# pad2console.net
KiCad netlist of a schematic drawn in EAGLE
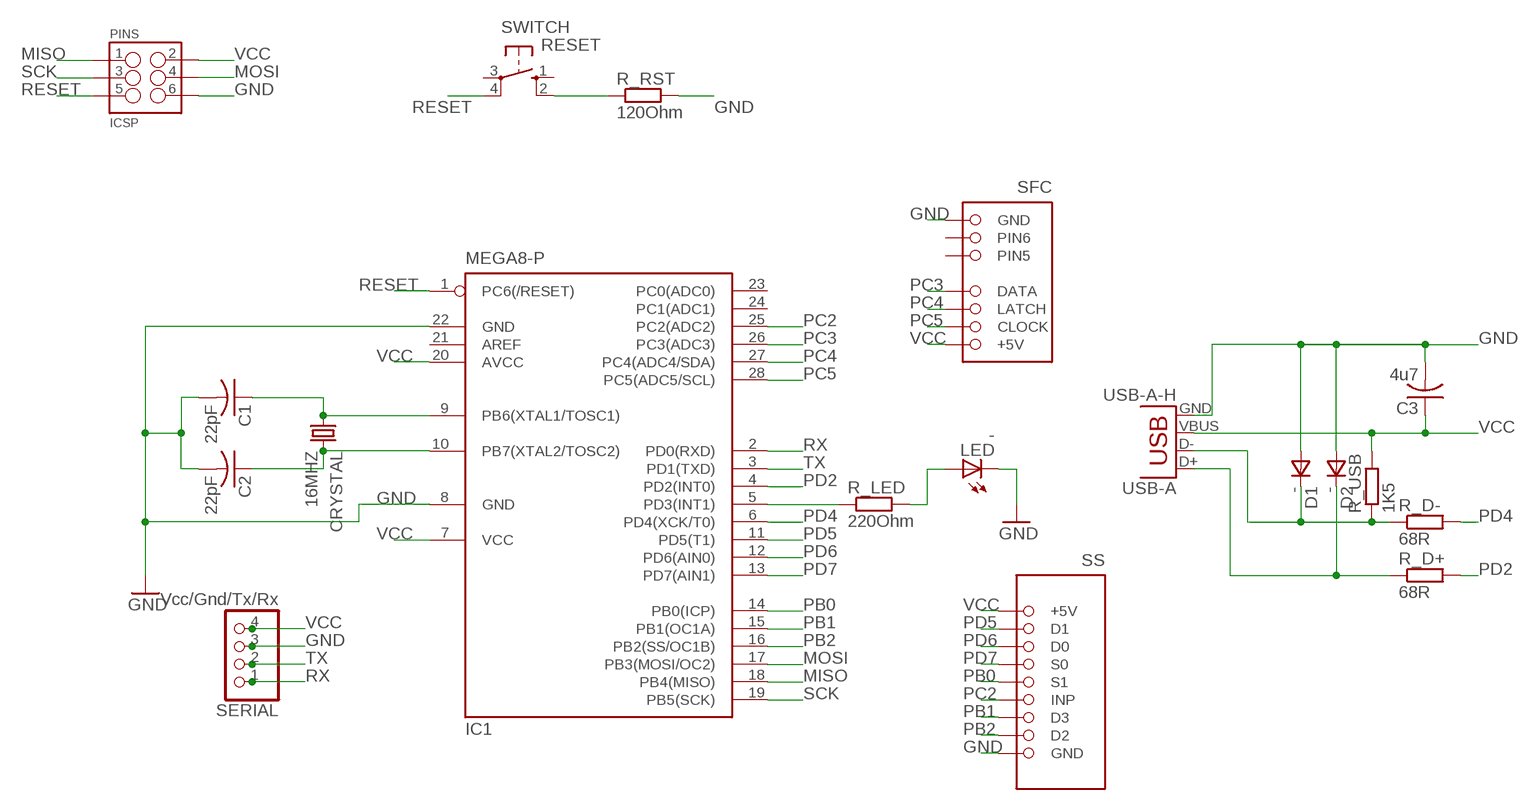
[diagram p0: schematic, sheet 1]

(export (version "E")
  (design (tool "Eeschema 10.0.6"))
  (components
    (comp (ref "C1")
      (value "22pF")
      (footprint "eagle-import:C050-024X044")
      (libsource (lib "eagle-import") (part "C-US050-024X044"))
    )
    (comp (ref "C2")
      (value "22pF")
      (footprint "eagle-import:C050-024X044")
      (libsource (lib "eagle-import") (part "C-US050-024X044"))
    )
    (comp (ref "C3")
      (value "4u7")
      (footprint "eagle-import:C050-024X044")
      (libsource (lib "eagle-import") (part "C-US050-024X044"))
    )
    (comp (ref "CRYSTAL")
      (value "16MHZ")
      (footprint "eagle-import:HC49_S")
      (libsource (lib "eagle-import") (part "CRYSTALHC49S"))
    )
    (comp (ref "D1")
      (value "-")
      (footprint "eagle-import:E2LINE")
      (libsource (lib "eagle-import") (part "D_E2L"))
    )
    (comp (ref "D2")
      (value "-")
      (footprint "eagle-import:E2LINE")
      (libsource (lib "eagle-import") (part "D_E2L"))
    )
    (comp (ref "IC1")
      (value "MEGA8-P")
      (footprint "eagle-import:DIL28-3")
      (libsource (lib "eagle-import") (part "MEGA8-P"))
    )
    (comp (ref "LED")
      (value "-")
      (footprint "eagle-import:LD260")
      (libsource (lib "eagle-import") (part "LEDLD260"))
    )
    (comp (ref "PINS")
      (value "ICSP")
      (footprint "eagle-import:2X3-SHROUDED")
      (libsource (lib "eagle-import") (part "M03X2SHROUD"))
    )
    (comp (ref "R_D+")
      (value "68R")
      (footprint "eagle-import:0204_5")
      (libsource (lib "eagle-import") (part "R-EU_0204/5"))
    )
    (comp (ref "R_D-")
      (value "68R")
      (footprint "eagle-import:0204_5")
      (libsource (lib "eagle-import") (part "R-EU_0204/5"))
    )
    (comp (ref "R_LED")
      (value "220Ohm")
      (footprint "eagle-import:0204_5")
      (libsource (lib "eagle-import") (part "R-EU_0204/5"))
    )
    (comp (ref "R_RST")
      (value "120Ohm")
      (footprint "eagle-import:0204_5")
      (libsource (lib "eagle-import") (part "R-EU_0204/5"))
    )
    (comp (ref "R_USB")
      (value "1K5")
      (footprint "eagle-import:0204_5")
      (libsource (lib "eagle-import") (part "R-EU_0204/5"))
    )
    (comp (ref "SERIAL")
      (value "Vcc/Gnd/Tx/Rx")
      (footprint "eagle-import:1X04")
      (libsource (lib "eagle-import") (part "PINHD-1X4"))
    )
    (comp (ref "SFC")
      (value "SFC_PIN")
      (footprint "eagle-import:SFC_PIN")
      (libsource (lib "eagle-import") (part "SFC_PIN"))
    )
    (comp (ref "SS")
      (value "SS_PIN")
      (footprint "eagle-import:SS_PIN")
      (libsource (lib "eagle-import") (part "SS_PIN"))
    )
    (comp (ref "SWITCH")
      (value "RESET")
      (footprint "eagle-import:B3F-10XX")
      (fields (field (name "MPN") "B3F-1000"))
      (libsource (lib "eagle-import") (part "10-XX"))
    )
    (comp (ref "USB-A")
      (value "USB-A-H")
      (footprint "eagle-import:USB-A-H")
      (libsource (lib "eagle-import") (part "USB-A-H"))
    )
  )
  (nets
    (net (code "1") (name "/MISO") (class "Default")
      (node (ref "IC1") (pin "18") (pinfunction "PB4(MISO)_18") (pintype "bidirectional"))
      (node (ref "PINS") (pin "1") (pinfunction "1_1") (pintype "bidirectional"))
    )
    (net (code "2") (name "/MOSI") (class "Default")
      (node (ref "IC1") (pin "17") (pinfunction "PB3(MOSI/OC2)_17") (pintype "bidirectional"))
      (node (ref "PINS") (pin "4") (pinfunction "4_4") (pintype "bidirectional"))
    )
    (net (code "3") (name "/PB0") (class "Default")
      (node (ref "IC1") (pin "14") (pinfunction "PB0(ICP)_14") (pintype "bidirectional"))
      (node (ref "SS") (pin "PIN5") (pinfunction "S1_PIN5") (pintype "bidirectional"))
    )
    (net (code "4") (name "/PB1") (class "Default")
      (node (ref "IC1") (pin "15") (pinfunction "PB1(OC1A)_15") (pintype "bidirectional"))
      (node (ref "SS") (pin "PIN7") (pinfunction "D3_PIN7") (pintype "bidirectional"))
    )
    (net (code "5") (name "/PB2") (class "Default")
      (node (ref "IC1") (pin "16") (pinfunction "PB2(SS/OC1B)_16") (pintype "bidirectional"))
      (node (ref "SS") (pin "PIN8") (pinfunction "D2_PIN8") (pintype "bidirectional"))
    )
    (net (code "6") (name "/PC2") (class "Default")
      (node (ref "IC1") (pin "25") (pinfunction "PC2(ADC2)_25") (pintype "bidirectional"))
      (node (ref "SS") (pin "PIN6") (pinfunction "INP_PIN6") (pintype "bidirectional"))
    )
    (net (code "7") (name "/PC3") (class "Default")
      (node (ref "IC1") (pin "26") (pinfunction "PC3(ADC3)_26") (pintype "bidirectional"))
      (node (ref "SFC") (pin "PIN4") (pinfunction "DATA_PIN4") (pintype "bidirectional"))
    )
    (net (code "8") (name "/PC4") (class "Default")
      (node (ref "IC1") (pin "27") (pinfunction "PC4(ADC4/SDA)_27") (pintype "bidirectional"))
      (node (ref "SFC") (pin "PIN3") (pinfunction "LATCH_PIN3") (pintype "bidirectional"))
    )
    (net (code "9") (name "/PC5") (class "Default")
      (node (ref "IC1") (pin "28") (pinfunction "PC5(ADC5/SCL)_28") (pintype "bidirectional"))
      (node (ref "SFC") (pin "PIN2") (pinfunction "CLOCK_PIN2") (pintype "bidirectional"))
    )
    (net (code "10") (name "/PD2") (class "Default")
      (node (ref "IC1") (pin "4") (pinfunction "PD2(INT0)_4") (pintype "bidirectional"))
      (node (ref "R_D+") (pin "2") (pinfunction "2_2") (pintype "passive"))
    )
    (net (code "11") (name "/PD4") (class "Default")
      (node (ref "IC1") (pin "6") (pinfunction "PD4(XCK/T0)_6") (pintype "bidirectional"))
      (node (ref "R_D-") (pin "2") (pinfunction "2_2") (pintype "passive"))
    )
    (net (code "12") (name "/PD5") (class "Default")
      (node (ref "IC1") (pin "11") (pinfunction "PD5(T1)_11") (pintype "bidirectional"))
      (node (ref "SS") (pin "PIN2") (pinfunction "D1_PIN2") (pintype "bidirectional"))
    )
    (net (code "13") (name "/PD6") (class "Default")
      (node (ref "IC1") (pin "12") (pinfunction "PD6(AIN0)_12") (pintype "bidirectional"))
      (node (ref "SS") (pin "PIN3") (pinfunction "D0_PIN3") (pintype "bidirectional"))
    )
    (net (code "14") (name "/PD7") (class "Default")
      (node (ref "IC1") (pin "13") (pinfunction "PD7(AIN1)_13") (pintype "bidirectional"))
      (node (ref "SS") (pin "PIN4") (pinfunction "S0_PIN4") (pintype "bidirectional"))
    )
    (net (code "15") (name "/RESET") (class "Default")
      (node (ref "IC1") (pin "1") (pinfunction "PC6(/RESET)_1") (pintype "bidirectional"))
      (node (ref "PINS") (pin "5") (pinfunction "5_5") (pintype "bidirectional"))
      (node (ref "SWITCH") (pin "4") (pinfunction "P1_4") (pintype "passive"))
    )
    (net (code "16") (name "/RX") (class "Default")
      (node (ref "IC1") (pin "2") (pinfunction "PD0(RXD)_2") (pintype "bidirectional"))
      (node (ref "SERIAL") (pin "1") (pinfunction "1_1") (pintype "passive"))
    )
    (net (code "17") (name "/SCK") (class "Default")
      (node (ref "IC1") (pin "19") (pinfunction "PB5(SCK)_19") (pintype "bidirectional"))
      (node (ref "PINS") (pin "3") (pinfunction "3_3") (pintype "bidirectional"))
    )
    (net (code "18") (name "/TX") (class "Default")
      (node (ref "IC1") (pin "3") (pinfunction "PD1(TXD)_3") (pintype "bidirectional"))
      (node (ref "SERIAL") (pin "2") (pinfunction "2_2") (pintype "passive"))
    )
    (net (code "19") (name "/VCC") (class "Default")
      (node (ref "C3") (pin "1") (pinfunction "1_1") (pintype "passive"))
      (node (ref "IC1") (pin "20") (pinfunction "AVCC_20") (pintype "power_in"))
      (node (ref "IC1") (pin "7") (pinfunction "VCC_7") (pintype "power_in"))
      (node (ref "PINS") (pin "2") (pinfunction "2_2") (pintype "bidirectional"))
      (node (ref "R_USB") (pin "2") (pinfunction "2_2") (pintype "passive"))
      (node (ref "SERIAL") (pin "4") (pinfunction "4_4") (pintype "passive"))
      (node (ref "SFC") (pin "PIN1") (pinfunction "+5V_PIN1") (pintype "bidirectional"))
      (node (ref "SS") (pin "PIN1") (pinfunction "+5V_PIN1") (pintype "bidirectional"))
      (node (ref "USB-A") (pin "VBUS") (pinfunction "VBUS_VBUS") (pintype "bidirectional"))
    )
    (net (code "20") (name "GND") (class "Default")
      (node (ref "C1") (pin "2") (pinfunction "2_2") (pintype "passive"))
      (node (ref "C2") (pin "2") (pinfunction "2_2") (pintype "passive"))
      (node (ref "C3") (pin "2") (pinfunction "2_2") (pintype "passive"))
      (node (ref "D1") (pin "2") (pinfunction "A_2") (pintype "passive"))
      (node (ref "D2") (pin "2") (pinfunction "A_2") (pintype "passive"))
      (node (ref "IC1") (pin "22") (pinfunction "GND_22") (pintype "power_in"))
      (node (ref "IC1") (pin "8") (pinfunction "GND_8") (pintype "power_in"))
      (node (ref "LED") (pin "K") (pinfunction "C_K") (pintype "passive"))
      (node (ref "PINS") (pin "6") (pinfunction "6_6") (pintype "bidirectional"))
      (node (ref "R_RST") (pin "2") (pinfunction "2_2") (pintype "passive"))
      (node (ref "SERIAL") (pin "3") (pinfunction "3_3") (pintype "passive"))
      (node (ref "SFC") (pin "PIN7") (pinfunction "GND_PIN7") (pintype "bidirectional"))
      (node (ref "SS") (pin "PIN9") (pinfunction "GND_PIN9") (pintype "bidirectional"))
      (node (ref "USB-A") (pin "GND") (pinfunction "GND_GND") (pintype "bidirectional"))
    )
    (net (code "21") (name "Net-(D1-C)") (class "Default")
      (node (ref "D1") (pin "1") (pinfunction "C_1") (pintype "passive"))
      (node (ref "R_D-") (pin "1") (pinfunction "1_1") (pintype "passive"))
      (node (ref "R_USB") (pin "1") (pinfunction "1_1") (pintype "passive"))
      (node (ref "USB-A") (pin "D-") (pinfunction "D-_D-") (pintype "bidirectional"))
    )
    (net (code "22") (name "Net-(D2-C)") (class "Default")
      (node (ref "D2") (pin "1") (pinfunction "C_1") (pintype "passive"))
      (node (ref "R_D+") (pin "1") (pinfunction "1_1") (pintype "passive"))
      (node (ref "USB-A") (pin "D+") (pinfunction "D+_D+") (pintype "bidirectional"))
    )
    (net (code "23") (name "Net-(IC1-PB6(XTAL1{slash}TOSC1))") (class "Default")
      (node (ref "C1") (pin "1") (pinfunction "1_1") (pintype "passive"))
      (node (ref "CRYSTAL") (pin "1") (pinfunction "1_1") (pintype "passive"))
      (node (ref "IC1") (pin "9") (pinfunction "PB6(XTAL1/TOSC1)_9") (pintype "bidirectional"))
    )
    (net (code "24") (name "Net-(IC1-PB7(XTAL2{slash}TOSC2))") (class "Default")
      (node (ref "C2") (pin "1") (pinfunction "1_1") (pintype "passive"))
      (node (ref "CRYSTAL") (pin "2") (pinfunction "2_2") (pintype "passive"))
      (node (ref "IC1") (pin "10") (pinfunction "PB7(XTAL2/TOSC2)_10") (pintype "bidirectional"))
    )
    (net (code "25") (name "Net-(IC1-PD3(INT1))") (class "Default")
      (node (ref "IC1") (pin "5") (pinfunction "PD3(INT1)_5") (pintype "bidirectional"))
      (node (ref "R_LED") (pin "1") (pinfunction "1_1") (pintype "passive"))
    )
    (net (code "26") (name "Net-(LED-PadA)") (class "Default")
      (node (ref "LED") (pin "A") (pinfunction "A_A") (pintype "passive"))
      (node (ref "R_LED") (pin "2") (pinfunction "2_2") (pintype "passive"))
    )
    (net (code "27") (name "Net-(SWITCH-S1)") (class "Default")
      (node (ref "R_RST") (pin "1") (pinfunction "1_1") (pintype "passive"))
      (node (ref "SWITCH") (pin "2") (pinfunction "S1_2") (pintype "passive"))
    )
    (net (code "28") (name "unconnected-(IC1-AREF-Pad21)") (class "Default")
      (node (ref "IC1") (pin "21") (pinfunction "AREF_21") (pintype "passive"))
    )
    (net (code "29") (name "unconnected-(IC1-PC0(ADC0)-Pad23)") (class "Default")
      (node (ref "IC1") (pin "23") (pinfunction "PC0(ADC0)_23") (pintype "bidirectional"))
    )
    (net (code "30") (name "unconnected-(IC1-PC1(ADC1)-Pad24)") (class "Default")
      (node (ref "IC1") (pin "24") (pinfunction "PC1(ADC1)_24") (pintype "bidirectional"))
    )
    (net (code "31") (name "unconnected-(SFC-PadPIN5)") (class "Default")
      (node (ref "SFC") (pin "PIN5") (pinfunction "PIN5_PIN5") (pintype "bidirectional"))
    )
    (net (code "32") (name "unconnected-(SFC-PadPIN6)") (class "Default")
      (node (ref "SFC") (pin "PIN6") (pinfunction "PIN6_PIN6") (pintype "bidirectional"))
    )
    (net (code "33") (name "unconnected-(SS-PadG1)") (class "Default")
      (node (ref "SS") (pin "G1") (pinfunction "G1_G1") (pintype "bidirectional"))
    )
    (net (code "34") (name "unconnected-(SS-PadG2)") (class "Default")
      (node (ref "SS") (pin "G2") (pinfunction "G2_G2") (pintype "bidirectional"))
    )
    (net (code "35") (name "unconnected-(SWITCH-P-Pad3)") (class "Default")
      (node (ref "SWITCH") (pin "3") (pinfunction "P_3") (pintype "passive"))
    )
    (net (code "36") (name "unconnected-(SWITCH-S-Pad1)") (class "Default")
      (node (ref "SWITCH") (pin "1") (pinfunction "S_1") (pintype "passive"))
    )
  )
)
